# IR2111_IRFZ44.net
KiCad netlist of a schematic drawn in Altium Designer
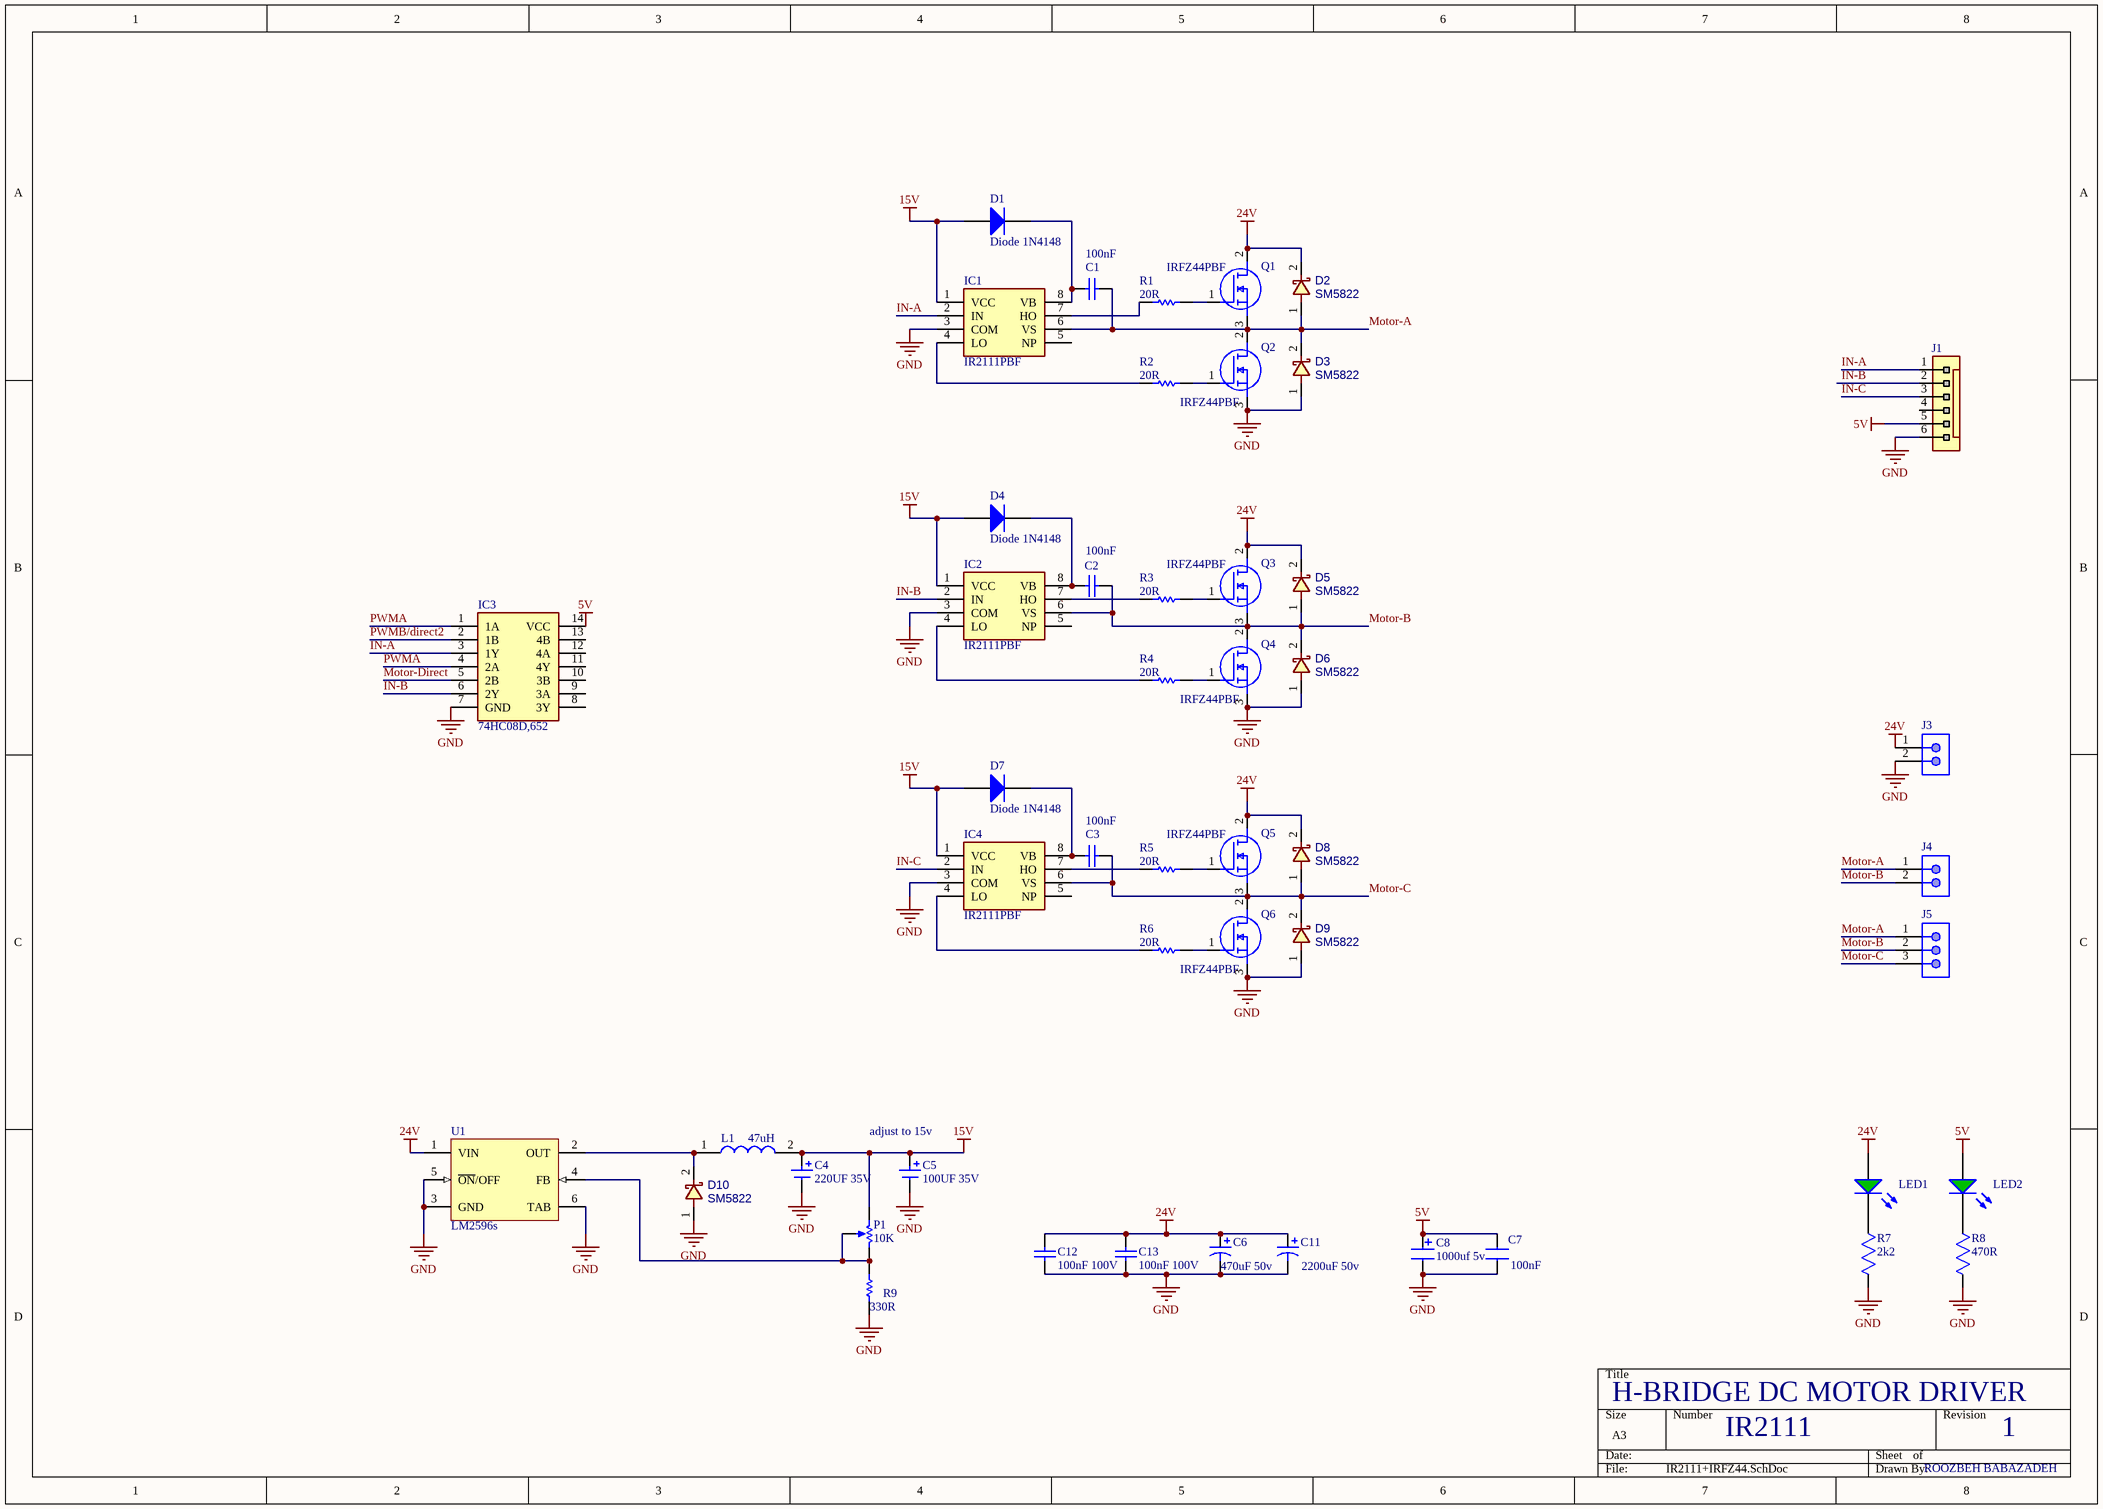
[diagram p0: IR2111+IRFZ44.SchDoc]

(export (version "E")
  (design (tool "Eeschema 10.0.6"))
  (components
    (comp (ref "C1")
      (value "100nF")
      (footprint "C0805")
      (description "Capacitor")
      (fields (field (name "PUBLISHER") "Altium Limited"))
      (libsource (lib "Miscellaneous Devices") (part "Cap"))
    )
    (comp (ref "C2")
      (value "100nF")
      (footprint "C0805")
      (description "Capacitor")
      (fields (field (name "PUBLISHER") "Altium Limited"))
      (libsource (lib "Miscellaneous Devices") (part "Cap"))
    )
    (comp (ref "C3")
      (value "100nF")
      (footprint "C0805")
      (description "Capacitor")
      (fields (field (name "PUBLISHER") "Altium Limited"))
      (libsource (lib "Miscellaneous Devices") (part "Cap"))
    )
    (comp (ref "C4")
      (value "220UF 35V")
      (footprint "C_EL_8X12")
      (libsource (lib "OTHER") (part "CAP_ELECTRO_POLIMER"))
    )
    (comp (ref "C5")
      (value "100UF 35V")
      (footprint "C_EL_8X12")
      (libsource (lib "OTHER") (part "CAP_ELECTRO_POLIMER"))
    )
    (comp (ref "C6")
      (value "470uF 50v")
      (footprint "C_EL_10X12")
      (description "63VDC")
      (libsource (lib "My_LIB") (part "Cap 220uF"))
    )
    (comp (ref "C7") (value "100nF") (footprint "C0805") (libsource (lib "OTHER") (part "C")))
    (comp (ref "C8") (value "1000uf 5v") (footprint "C_EL_8X12") (libsource (lib "OTHER") (part "CAP3528")))
    (comp (ref "C11")
      (value "2200uF 50v")
      (footprint "C_EL_16X25")
      (description "63VDC")
      (libsource (lib "My_LIB") (part "Cap 220uF"))
    )
    (comp (ref "C12")
      (value "100nF 100V")
      (footprint "C_CER_D7B")
      (libsource (lib "My_LIB") (part "Cap 100nF"))
    )
    (comp (ref "C13")
      (value "100nF 100V")
      (footprint "C_CER_D7B")
      (description "63VDC")
      (fields (field (name "PUBLISHER") "Altium Limited"))
      (libsource (lib "Miscellaneous Devices") (part "Cap"))
    )
    (comp (ref "D1")
      (value "Diode 1N4148")
      (footprint "D_SOD123W")
      (fields (field (name "PUBLISHER") "Altium Limited"))
      (libsource (lib "Miscellaneous Devices") (part "Diode 1N4005"))
    )
    (comp (ref "D2")
      (value "SM5822")
      (footprint "D_SMB")
      (description "DIODE, SCHOTTKY, 50V, 3A")
      (fields (field (name "MANF") "DIODES") (field (name "MANF_P#") "1N5819HW-7-F"))
      (libsource (lib "diode") (part "SCHOTTKY"))
    )
    (comp (ref "D3")
      (value "SM5822")
      (footprint "D_SMB")
      (description "DIODE, SCHOTTKY, 50V, 3A")
      (fields (field (name "MANF") "DIODES") (field (name "MANF_P#") "1N5819HW-7-F"))
      (libsource (lib "diode") (part "SCHOTTKY"))
    )
    (comp (ref "D4")
      (value "Diode 1N4148")
      (footprint "D_SOD123W")
      (description "1 Amp General Purpose Rectifier")
      (fields (field (name "PUBLISHER") "Altium Limited"))
      (libsource (lib "Miscellaneous Devices") (part "Diode 1N4005"))
    )
    (comp (ref "D5")
      (value "SM5822")
      (footprint "D_SMB")
      (description "DIODE, SCHOTTKY, 50V, 3A")
      (fields (field (name "MANF") "DIODES") (field (name "MANF_P#") "1N5819HW-7-F"))
      (libsource (lib "diode") (part "SCHOTTKY"))
    )
    (comp (ref "D6")
      (value "SM5822")
      (footprint "D_SMB")
      (description "DIODE, SCHOTTKY, 50V, 3A")
      (fields (field (name "MANF") "DIODES") (field (name "MANF_P#") "1N5819HW-7-F"))
      (libsource (lib "diode") (part "SCHOTTKY"))
    )
    (comp (ref "D7")
      (value "Diode 1N4148")
      (footprint "D_SOD123W")
      (description "1 Amp General Purpose Rectifier")
      (fields (field (name "PUBLISHER") "Altium Limited"))
      (libsource (lib "Miscellaneous Devices") (part "Diode 1N4005"))
    )
    (comp (ref "D8")
      (value "SM5822")
      (footprint "D_SMB")
      (description "DIODE, SCHOTTKY, 50V, 3A")
      (fields (field (name "MANF") "DIODES") (field (name "MANF_P#") "1N5819HW-7-F"))
      (libsource (lib "diode") (part "SCHOTTKY"))
    )
    (comp (ref "D9")
      (value "SM5822")
      (footprint "D_SMB")
      (description "DIODE, SCHOTTKY, 50V, 3A")
      (fields (field (name "MANF") "DIODES") (field (name "MANF_P#") "1N5819HW-7-F"))
      (libsource (lib "diode") (part "SCHOTTKY"))
    )
    (comp (ref "D10")
      (value "SM5822")
      (footprint "D_SMB")
      (description "DIODE, SCHOTTKY, 50V, 3A")
      (fields (field (name "MANF") "DIODES") (field (name "MANF_P#") "1N5819HW-7-F"))
      (libsource (lib "diode") (part "SCHOTTKY"))
    )
    (comp (ref "IC1")
      (value "IR2111PBF")
      (footprint "SO_8")
      (description "Integrated Circuit")
      (fields (field (name "MOUSER PART NUMBER") "942-IR2111PBF"))
      (libsource (lib "*") (part "IR2111PBF"))
    )
    (comp (ref "IC2")
      (value "IR2111PBF")
      (footprint "SO_8")
      (description "Integrated Circuit")
      (fields (field (name "MOUSER PART NUMBER") "942-IR2111PBF"))
      (libsource (lib "*") (part "IR2111PBF"))
    )
    (comp (ref "IC3")
      (value "74HC08D,652")
      (footprint "SO_14")
      (description "Integrated Circuit")
      (fields (field (name "MOUSER PART NUMBER") "771-HC08D652"))
      (libsource (lib "*") (part "74HC08D,652"))
    )
    (comp (ref "IC4")
      (value "IR2111PBF")
      (footprint "SO_8")
      (description "Integrated Circuit")
      (fields (field (name "MOUSER PART NUMBER") "942-IR2111PBF"))
      (libsource (lib "*") (part "IR2111PBF"))
    )
    (comp (ref "J1")
      (value "HDRWF_6")
      (footprint "WF_6")
      (description "Header, WF, Pitch: 2.54mm")
      (libsource (lib "xh-xhr-wf-hhdr-hh6r") (part "HDRWF_6"))
    )
    (comp (ref "J3")
      (value "2PIN  3.96")
      (footprint "PWL_2")
      (description "wire to board pitch 3.96 mm CH series")
      (fields (field (name "PART NUMBER") "61300211121") (field (name "PUBLISHER") "Wurth Elektronik"))
      (libsource (lib "sip m") (part "sip 2"))
    )
    (comp (ref "J4")
      (value "2PIN  3.96")
      (footprint "PWL_2")
      (description "wire to board pitch 3.96 mm CH series")
      (fields (field (name "PART NUMBER") "61300211121") (field (name "PUBLISHER") "Wurth Elektronik"))
      (libsource (lib "sip m") (part "sip 2"))
    )
    (comp (ref "J5")
      (value "3PIN  3.96")
      (footprint "PWL_3")
      (description "wire to board pitch 3.96 mm CH series")
      (fields (field (name "PART NUMBER") "61300311121") (field (name "PUBLISHER") "Wurth Elektronik"))
      (libsource (lib "sip m") (part "sip 3"))
    )
    (comp (ref "L1")
      (value "47uH")
      (footprint "CDRH127LDNP560MC-12*12")
      (description "Inductor")
      (fields
        (field (name "MANUFACTURER_PART_NUMBER") "CDRH127/LDNP-560MC")
        (field (name "MOUSER PART NUMBER") "851-CDRH127LDNP560MC")
      )
      (libsource (lib "*") (part "CDRH127_LDNP-560MC"))
    )
    (comp (ref "LED1") (value "~") (footprint "LED1206RED") (libsource (lib "OTHER") (part "LED3mm")))
    (comp (ref "LED2") (value "~") (footprint "LED1206RED") (libsource (lib "OTHER") (part "LED3mm")))
    (comp (ref "P1")
      (value "10K")
      (footprint "POT_3296W")
      (description "Potentiometer")
      (libsource (lib "My_LIB") (part "Multi-Turn"))
    )
    (comp (ref "Q1")
      (value "IRFZ44PBF")
      (footprint "D2PAK3")
      (description "MOSFET (N-Channel)")
      (fields (field (name "MOUSER PART NUMBER") "844-IRFZ44PBF"))
      (libsource (lib "*") (part "IRFZ44PBF"))
    )
    (comp (ref "Q2")
      (value "IRFZ44PBF")
      (footprint "D2PAK3")
      (description "MOSFET (N-Channel)")
      (fields (field (name "MOUSER PART NUMBER") "844-IRFZ44PBF"))
      (libsource (lib "*") (part "IRFZ44PBF"))
    )
    (comp (ref "Q3")
      (value "IRFZ44PBF")
      (footprint "D2PAK3")
      (description "MOSFET (N-Channel)")
      (fields (field (name "MOUSER PART NUMBER") "844-IRFZ44PBF"))
      (libsource (lib "*") (part "IRFZ44PBF"))
    )
    (comp (ref "Q4")
      (value "IRFZ44PBF")
      (footprint "D2PAK3")
      (description "MOSFET (N-Channel)")
      (fields (field (name "MOUSER PART NUMBER") "844-IRFZ44PBF"))
      (libsource (lib "*") (part "IRFZ44PBF"))
    )
    (comp (ref "Q5")
      (value "IRFZ44PBF")
      (footprint "D2PAK3")
      (description "MOSFET (N-Channel)")
      (fields (field (name "MOUSER PART NUMBER") "844-IRFZ44PBF"))
      (libsource (lib "*") (part "IRFZ44PBF"))
    )
    (comp (ref "Q6")
      (value "IRFZ44PBF")
      (footprint "D2PAK3")
      (description "MOSFET (N-Channel)")
      (fields (field (name "MOUSER PART NUMBER") "844-IRFZ44PBF"))
      (libsource (lib "*") (part "IRFZ44PBF"))
    )
    (comp (ref "R1")
      (value "20R")
      (footprint "R0805")
      (description "Resistor")
      (fields (field (name "PUBLISHER") "Altium Limited"))
      (libsource (lib "Miscellaneous Devices") (part "Res1"))
    )
    (comp (ref "R2")
      (value "20R")
      (footprint "R0805")
      (description "Resistor")
      (fields (field (name "PUBLISHER") "Altium Limited"))
      (libsource (lib "Miscellaneous Devices") (part "Res1"))
    )
    (comp (ref "R3")
      (value "20R")
      (footprint "R0805")
      (description "Resistor")
      (fields (field (name "PUBLISHER") "Altium Limited"))
      (libsource (lib "Miscellaneous Devices") (part "Res1"))
    )
    (comp (ref "R4")
      (value "20R")
      (footprint "R0805")
      (description "Resistor")
      (fields (field (name "PUBLISHER") "Altium Limited"))
      (libsource (lib "Miscellaneous Devices") (part "Res1"))
    )
    (comp (ref "R5")
      (value "20R")
      (footprint "R0805")
      (description "Resistor")
      (fields (field (name "PUBLISHER") "Altium Limited"))
      (libsource (lib "Miscellaneous Devices") (part "Res1"))
    )
    (comp (ref "R6")
      (value "20R")
      (footprint "R0805")
      (description "Resistor")
      (fields (field (name "PUBLISHER") "Altium Limited"))
      (libsource (lib "Miscellaneous Devices") (part "Res1"))
    )
    (comp (ref "R7") (value "2k2") (footprint "R0805") (libsource (lib "OTHER") (part "R")))
    (comp (ref "R8") (value "470R") (footprint "R0805") (libsource (lib "OTHER") (part "R")))
    (comp (ref "R9")
      (value "330R")
      (footprint "R0805")
      (description "Resistor")
      (fields (field (name "PUBLISHER") "Altium Limited"))
      (libsource (lib "Miscellaneous Devices") (part "Res1"))
    )
    (comp (ref "U1")
      (value "LM2596s")
      (footprint "to-263-5 5d2pak LM2596S")
      (libsource (lib "POWER") (part "LM2596s"))
    )
  )
  (nets
    (net (code "1") (name "/IN-A") (class "Default")
      (node (ref "IC1") (pin "2") (pinfunction "IN_2") (pintype "passive"))
      (node (ref "IC3") (pin "3") (pinfunction "1Y_3") (pintype "passive"))
      (node (ref "J1") (pin "1") (pinfunction "1_1") (pintype "passive"))
    )
    (net (code "2") (name "/IN-B") (class "Default")
      (node (ref "IC2") (pin "2") (pinfunction "IN_2") (pintype "passive"))
      (node (ref "IC3") (pin "6") (pinfunction "2Y_6") (pintype "passive"))
      (node (ref "J1") (pin "2") (pinfunction "2_2") (pintype "passive"))
    )
    (net (code "3") (name "/IN-C") (class "Default")
      (node (ref "IC4") (pin "2") (pinfunction "IN_2") (pintype "passive"))
      (node (ref "J1") (pin "3") (pinfunction "3_3") (pintype "passive"))
    )
    (net (code "4") (name "/Motor-A") (class "Default")
      (node (ref "C1") (pin "1") (pinfunction "1_1") (pintype "passive"))
      (node (ref "D2") (pin "1") (pinfunction "1_1") (pintype "passive"))
      (node (ref "D3") (pin "2") (pinfunction "2_2") (pintype "passive"))
      (node (ref "IC1") (pin "6") (pinfunction "VS_6") (pintype "passive"))
      (node (ref "J4") (pin "1") (pinfunction "1_1") (pintype "passive"))
      (node (ref "J5") (pin "1") (pinfunction "1_1") (pintype "passive"))
      (node (ref "Q1") (pin "3") (pinfunction "S_3") (pintype "passive"))
      (node (ref "Q2") (pin "2") (pinfunction "D_2") (pintype "passive"))
    )
    (net (code "5") (name "/Motor-B") (class "Default")
      (node (ref "C2") (pin "1") (pinfunction "1_1") (pintype "passive"))
      (node (ref "D5") (pin "1") (pinfunction "1_1") (pintype "passive"))
      (node (ref "D6") (pin "2") (pinfunction "2_2") (pintype "passive"))
      (node (ref "IC2") (pin "6") (pinfunction "VS_6") (pintype "passive"))
      (node (ref "J4") (pin "2") (pinfunction "2_2") (pintype "passive"))
      (node (ref "J5") (pin "2") (pinfunction "2_2") (pintype "passive"))
      (node (ref "Q3") (pin "3") (pinfunction "S_3") (pintype "passive"))
      (node (ref "Q4") (pin "2") (pinfunction "D_2") (pintype "passive"))
    )
    (net (code "6") (name "/Motor-C") (class "Default")
      (node (ref "C3") (pin "1") (pinfunction "1_1") (pintype "passive"))
      (node (ref "D8") (pin "1") (pinfunction "1_1") (pintype "passive"))
      (node (ref "D9") (pin "2") (pinfunction "2_2") (pintype "passive"))
      (node (ref "IC4") (pin "6") (pinfunction "VS_6") (pintype "passive"))
      (node (ref "J5") (pin "3") (pinfunction "3_3") (pintype "passive"))
      (node (ref "Q5") (pin "3") (pinfunction "S_3") (pintype "passive"))
      (node (ref "Q6") (pin "2") (pinfunction "D_2") (pintype "passive"))
    )
    (net (code "7") (name "/Motor-Direct") (class "Default")
      (node (ref "IC3") (pin "5") (pinfunction "2B_5") (pintype "passive"))
    )
    (net (code "8") (name "/PWMA") (class "Default")
      (node (ref "IC3") (pin "1") (pinfunction "1A_1") (pintype "passive"))
      (node (ref "IC3") (pin "4") (pinfunction "2A_4") (pintype "passive"))
    )
    (net (code "9") (name "/PWMB{slash}direct2") (class "Default")
      (node (ref "IC3") (pin "2") (pinfunction "1B_2") (pintype "passive"))
    )
    (net (code "10") (name "5V") (class "Default")
      (node (ref "C7") (pin "2") (pintype "passive"))
      (node (ref "C8") (pin "1") (pinfunction "1_1") (pintype "passive"))
      (node (ref "IC3") (pin "14") (pinfunction "VCC_14") (pintype "passive"))
      (node (ref "J1") (pin "5") (pinfunction "5_5") (pintype "passive"))
      (node (ref "LED2") (pin "1") (pinfunction "A_1") (pintype "passive"))
    )
    (net (code "11") (name "15V") (class "Default")
      (node (ref "C4") (pin "1") (pinfunction "1_1") (pintype "passive"))
      (node (ref "C5") (pin "1") (pinfunction "1_1") (pintype "passive"))
      (node (ref "D1") (pin "1") (pinfunction "A_1") (pintype "passive"))
      (node (ref "D4") (pin "1") (pinfunction "A_1") (pintype "passive"))
      (node (ref "D7") (pin "1") (pinfunction "A_1") (pintype "passive"))
      (node (ref "IC1") (pin "1") (pinfunction "VCC_1") (pintype "passive"))
      (node (ref "IC2") (pin "1") (pinfunction "VCC_1") (pintype "passive"))
      (node (ref "IC4") (pin "1") (pinfunction "VCC_1") (pintype "passive"))
      (node (ref "L1") (pin "2") (pinfunction "2_2") (pintype "passive"))
      (node (ref "P1") (pin "3") (pinfunction "BOT_3") (pintype "passive"))
    )
    (net (code "12") (name "24V") (class "Default")
      (node (ref "C11") (pin "1") (pinfunction "1_1") (pintype "passive"))
      (node (ref "C12") (pin "2") (pinfunction "2_2") (pintype "passive"))
      (node (ref "C13") (pin "2") (pinfunction "2_2") (pintype "passive"))
      (node (ref "C6") (pin "1") (pinfunction "1_1") (pintype "passive"))
      (node (ref "D2") (pin "2") (pinfunction "2_2") (pintype "passive"))
      (node (ref "D5") (pin "2") (pinfunction "2_2") (pintype "passive"))
      (node (ref "D8") (pin "2") (pinfunction "2_2") (pintype "passive"))
      (node (ref "J3") (pin "1") (pinfunction "1_1") (pintype "passive"))
      (node (ref "LED1") (pin "1") (pinfunction "A_1") (pintype "passive"))
      (node (ref "Q1") (pin "2") (pinfunction "D_2") (pintype "passive"))
      (node (ref "Q3") (pin "2") (pinfunction "D_2") (pintype "passive"))
      (node (ref "Q5") (pin "2") (pinfunction "D_2") (pintype "passive"))
      (node (ref "U1") (pin "1") (pinfunction "VIN_1") (pintype "power_in"))
    )
    (net (code "13") (name "GND") (class "Default")
      (node (ref "C11") (pin "2") (pinfunction "2_2") (pintype "passive"))
      (node (ref "C12") (pin "1") (pinfunction "1_1") (pintype "passive"))
      (node (ref "C13") (pin "1") (pinfunction "1_1") (pintype "passive"))
      (node (ref "C4") (pin "2") (pinfunction "2_2") (pintype "passive"))
      (node (ref "C5") (pin "2") (pinfunction "2_2") (pintype "passive"))
      (node (ref "C6") (pin "2") (pinfunction "2_2") (pintype "passive"))
      (node (ref "C7") (pin "1") (pintype "passive"))
      (node (ref "C8") (pin "2") (pinfunction "2_2") (pintype "passive"))
      (node (ref "D10") (pin "1") (pinfunction "1_1") (pintype "passive"))
      (node (ref "D3") (pin "1") (pinfunction "1_1") (pintype "passive"))
      (node (ref "D6") (pin "1") (pinfunction "1_1") (pintype "passive"))
      (node (ref "D9") (pin "1") (pinfunction "1_1") (pintype "passive"))
      (node (ref "IC1") (pin "3") (pinfunction "COM_3") (pintype "passive"))
      (node (ref "IC2") (pin "3") (pinfunction "COM_3") (pintype "passive"))
      (node (ref "IC3") (pin "7") (pinfunction "GND_7") (pintype "passive"))
      (node (ref "IC4") (pin "3") (pinfunction "COM_3") (pintype "passive"))
      (node (ref "J1") (pin "6") (pinfunction "6_6") (pintype "passive"))
      (node (ref "J3") (pin "2") (pinfunction "2_2") (pintype "passive"))
      (node (ref "Q2") (pin "3") (pinfunction "S_3") (pintype "passive"))
      (node (ref "Q4") (pin "3") (pinfunction "S_3") (pintype "passive"))
      (node (ref "Q6") (pin "3") (pinfunction "S_3") (pintype "passive"))
      (node (ref "R7") (pin "2") (pintype "passive"))
      (node (ref "R8") (pin "2") (pintype "passive"))
      (node (ref "R9") (pin "1") (pinfunction "1_1") (pintype "passive"))
      (node (ref "U1") (pin "3") (pinfunction "GND_3") (pintype "power_in"))
      (node (ref "U1") (pin "5") (pinfunction "~{ON}/OFF_5") (pintype "input"))
      (node (ref "U1") (pin "6") (pinfunction "TAB_6") (pintype "power_in"))
    )
    (net (code "14") (name "Net-(D1-K)") (class "Default")
      (node (ref "C1") (pin "2") (pinfunction "2_2") (pintype "passive"))
      (node (ref "D1") (pin "2") (pinfunction "K_2") (pintype "passive"))
      (node (ref "IC1") (pin "8") (pinfunction "VB_8") (pintype "passive"))
    )
    (net (code "15") (name "Net-(D4-K)") (class "Default")
      (node (ref "C2") (pin "2") (pinfunction "2_2") (pintype "passive"))
      (node (ref "D4") (pin "2") (pinfunction "K_2") (pintype "passive"))
      (node (ref "IC2") (pin "8") (pinfunction "VB_8") (pintype "passive"))
    )
    (net (code "16") (name "Net-(D7-K)") (class "Default")
      (node (ref "C3") (pin "2") (pinfunction "2_2") (pintype "passive"))
      (node (ref "D7") (pin "2") (pinfunction "K_2") (pintype "passive"))
      (node (ref "IC4") (pin "8") (pinfunction "VB_8") (pintype "passive"))
    )
    (net (code "17") (name "Net-(IC1-HO)") (class "Default")
      (node (ref "IC1") (pin "7") (pinfunction "HO_7") (pintype "passive"))
      (node (ref "R1") (pin "1") (pinfunction "1_1") (pintype "passive"))
    )
    (net (code "18") (name "Net-(IC1-LO)") (class "Default")
      (node (ref "IC1") (pin "4") (pinfunction "LO_4") (pintype "passive"))
      (node (ref "R2") (pin "1") (pinfunction "1_1") (pintype "passive"))
    )
    (net (code "19") (name "Net-(IC2-HO)") (class "Default")
      (node (ref "IC2") (pin "7") (pinfunction "HO_7") (pintype "passive"))
      (node (ref "R3") (pin "1") (pinfunction "1_1") (pintype "passive"))
    )
    (net (code "20") (name "Net-(IC2-LO)") (class "Default")
      (node (ref "IC2") (pin "4") (pinfunction "LO_4") (pintype "passive"))
      (node (ref "R4") (pin "1") (pinfunction "1_1") (pintype "passive"))
    )
    (net (code "21") (name "Net-(IC4-HO)") (class "Default")
      (node (ref "IC4") (pin "7") (pinfunction "HO_7") (pintype "passive"))
      (node (ref "R5") (pin "1") (pinfunction "1_1") (pintype "passive"))
    )
    (net (code "22") (name "Net-(IC4-LO)") (class "Default")
      (node (ref "IC4") (pin "4") (pinfunction "LO_4") (pintype "passive"))
      (node (ref "R6") (pin "1") (pinfunction "1_1") (pintype "passive"))
    )
    (net (code "23") (name "Net-(LED1-K)") (class "Default")
      (node (ref "LED1") (pin "2") (pinfunction "K_2") (pintype "passive"))
      (node (ref "R7") (pin "1") (pintype "passive"))
    )
    (net (code "24") (name "Net-(LED2-K)") (class "Default")
      (node (ref "LED2") (pin "2") (pinfunction "K_2") (pintype "passive"))
      (node (ref "R8") (pin "1") (pintype "passive"))
    )
    (net (code "25") (name "Net-(P1-TAP)") (class "Default")
      (node (ref "P1") (pin "1") (pinfunction "TOP_1") (pintype "passive"))
      (node (ref "P1") (pin "2") (pinfunction "TAP_2") (pintype "passive"))
      (node (ref "R9") (pin "2") (pinfunction "2_2") (pintype "passive"))
      (node (ref "U1") (pin "4") (pinfunction "FB_4") (pintype "input"))
    )
    (net (code "26") (name "Net-(Q1-G)") (class "Default")
      (node (ref "Q1") (pin "1") (pinfunction "G_1") (pintype "passive"))
      (node (ref "R1") (pin "2") (pinfunction "2_2") (pintype "passive"))
    )
    (net (code "27") (name "Net-(Q2-G)") (class "Default")
      (node (ref "Q2") (pin "1") (pinfunction "G_1") (pintype "passive"))
      (node (ref "R2") (pin "2") (pinfunction "2_2") (pintype "passive"))
    )
    (net (code "28") (name "Net-(Q3-G)") (class "Default")
      (node (ref "Q3") (pin "1") (pinfunction "G_1") (pintype "passive"))
      (node (ref "R3") (pin "2") (pinfunction "2_2") (pintype "passive"))
    )
    (net (code "29") (name "Net-(Q4-G)") (class "Default")
      (node (ref "Q4") (pin "1") (pinfunction "G_1") (pintype "passive"))
      (node (ref "R4") (pin "2") (pinfunction "2_2") (pintype "passive"))
    )
    (net (code "30") (name "Net-(Q5-G)") (class "Default")
      (node (ref "Q5") (pin "1") (pinfunction "G_1") (pintype "passive"))
      (node (ref "R5") (pin "2") (pinfunction "2_2") (pintype "passive"))
    )
    (net (code "31") (name "Net-(Q6-G)") (class "Default")
      (node (ref "Q6") (pin "1") (pinfunction "G_1") (pintype "passive"))
      (node (ref "R6") (pin "2") (pinfunction "2_2") (pintype "passive"))
    )
    (net (code "32") (name "Net-(U1-OUT)") (class "Default")
      (node (ref "D10") (pin "2") (pinfunction "2_2") (pintype "passive"))
      (node (ref "L1") (pin "1") (pinfunction "1_1") (pintype "passive"))
      (node (ref "U1") (pin "2") (pinfunction "OUT_2") (pintype "power_in"))
    )
    (net (code "33") (name "unconnected-(IC1-NP-Pad5)") (class "Default")
      (node (ref "IC1") (pin "5") (pinfunction "NP_5") (pintype "passive"))
    )
    (net (code "34") (name "unconnected-(IC2-NP-Pad5)") (class "Default")
      (node (ref "IC2") (pin "5") (pinfunction "NP_5") (pintype "passive"))
    )
    (net (code "35") (name "unconnected-(IC3-3A-Pad9)") (class "Default")
      (node (ref "IC3") (pin "9") (pinfunction "3A_9") (pintype "passive"))
    )
    (net (code "36") (name "unconnected-(IC3-3B-Pad10)") (class "Default")
      (node (ref "IC3") (pin "10") (pinfunction "3B_10") (pintype "passive"))
    )
    (net (code "37") (name "unconnected-(IC3-3Y-Pad8)") (class "Default")
      (node (ref "IC3") (pin "8") (pinfunction "3Y_8") (pintype "passive"))
    )
    (net (code "38") (name "unconnected-(IC3-4A-Pad12)") (class "Default")
      (node (ref "IC3") (pin "12") (pinfunction "4A_12") (pintype "passive"))
    )
    (net (code "39") (name "unconnected-(IC3-4B-Pad13)") (class "Default")
      (node (ref "IC3") (pin "13") (pinfunction "4B_13") (pintype "passive"))
    )
    (net (code "40") (name "unconnected-(IC3-4Y-Pad11)") (class "Default")
      (node (ref "IC3") (pin "11") (pinfunction "4Y_11") (pintype "passive"))
    )
    (net (code "41") (name "unconnected-(IC4-NP-Pad5)") (class "Default")
      (node (ref "IC4") (pin "5") (pinfunction "NP_5") (pintype "passive"))
    )
    (net (code "42") (name "unconnected-(J1-Pad4)") (class "Default")
      (node (ref "J1") (pin "4") (pinfunction "4_4") (pintype "passive"))
    )
  )
)
